# DRV8701-sch-pcb.net
KiCad netlist of a schematic drawn in EasyEDA Pro
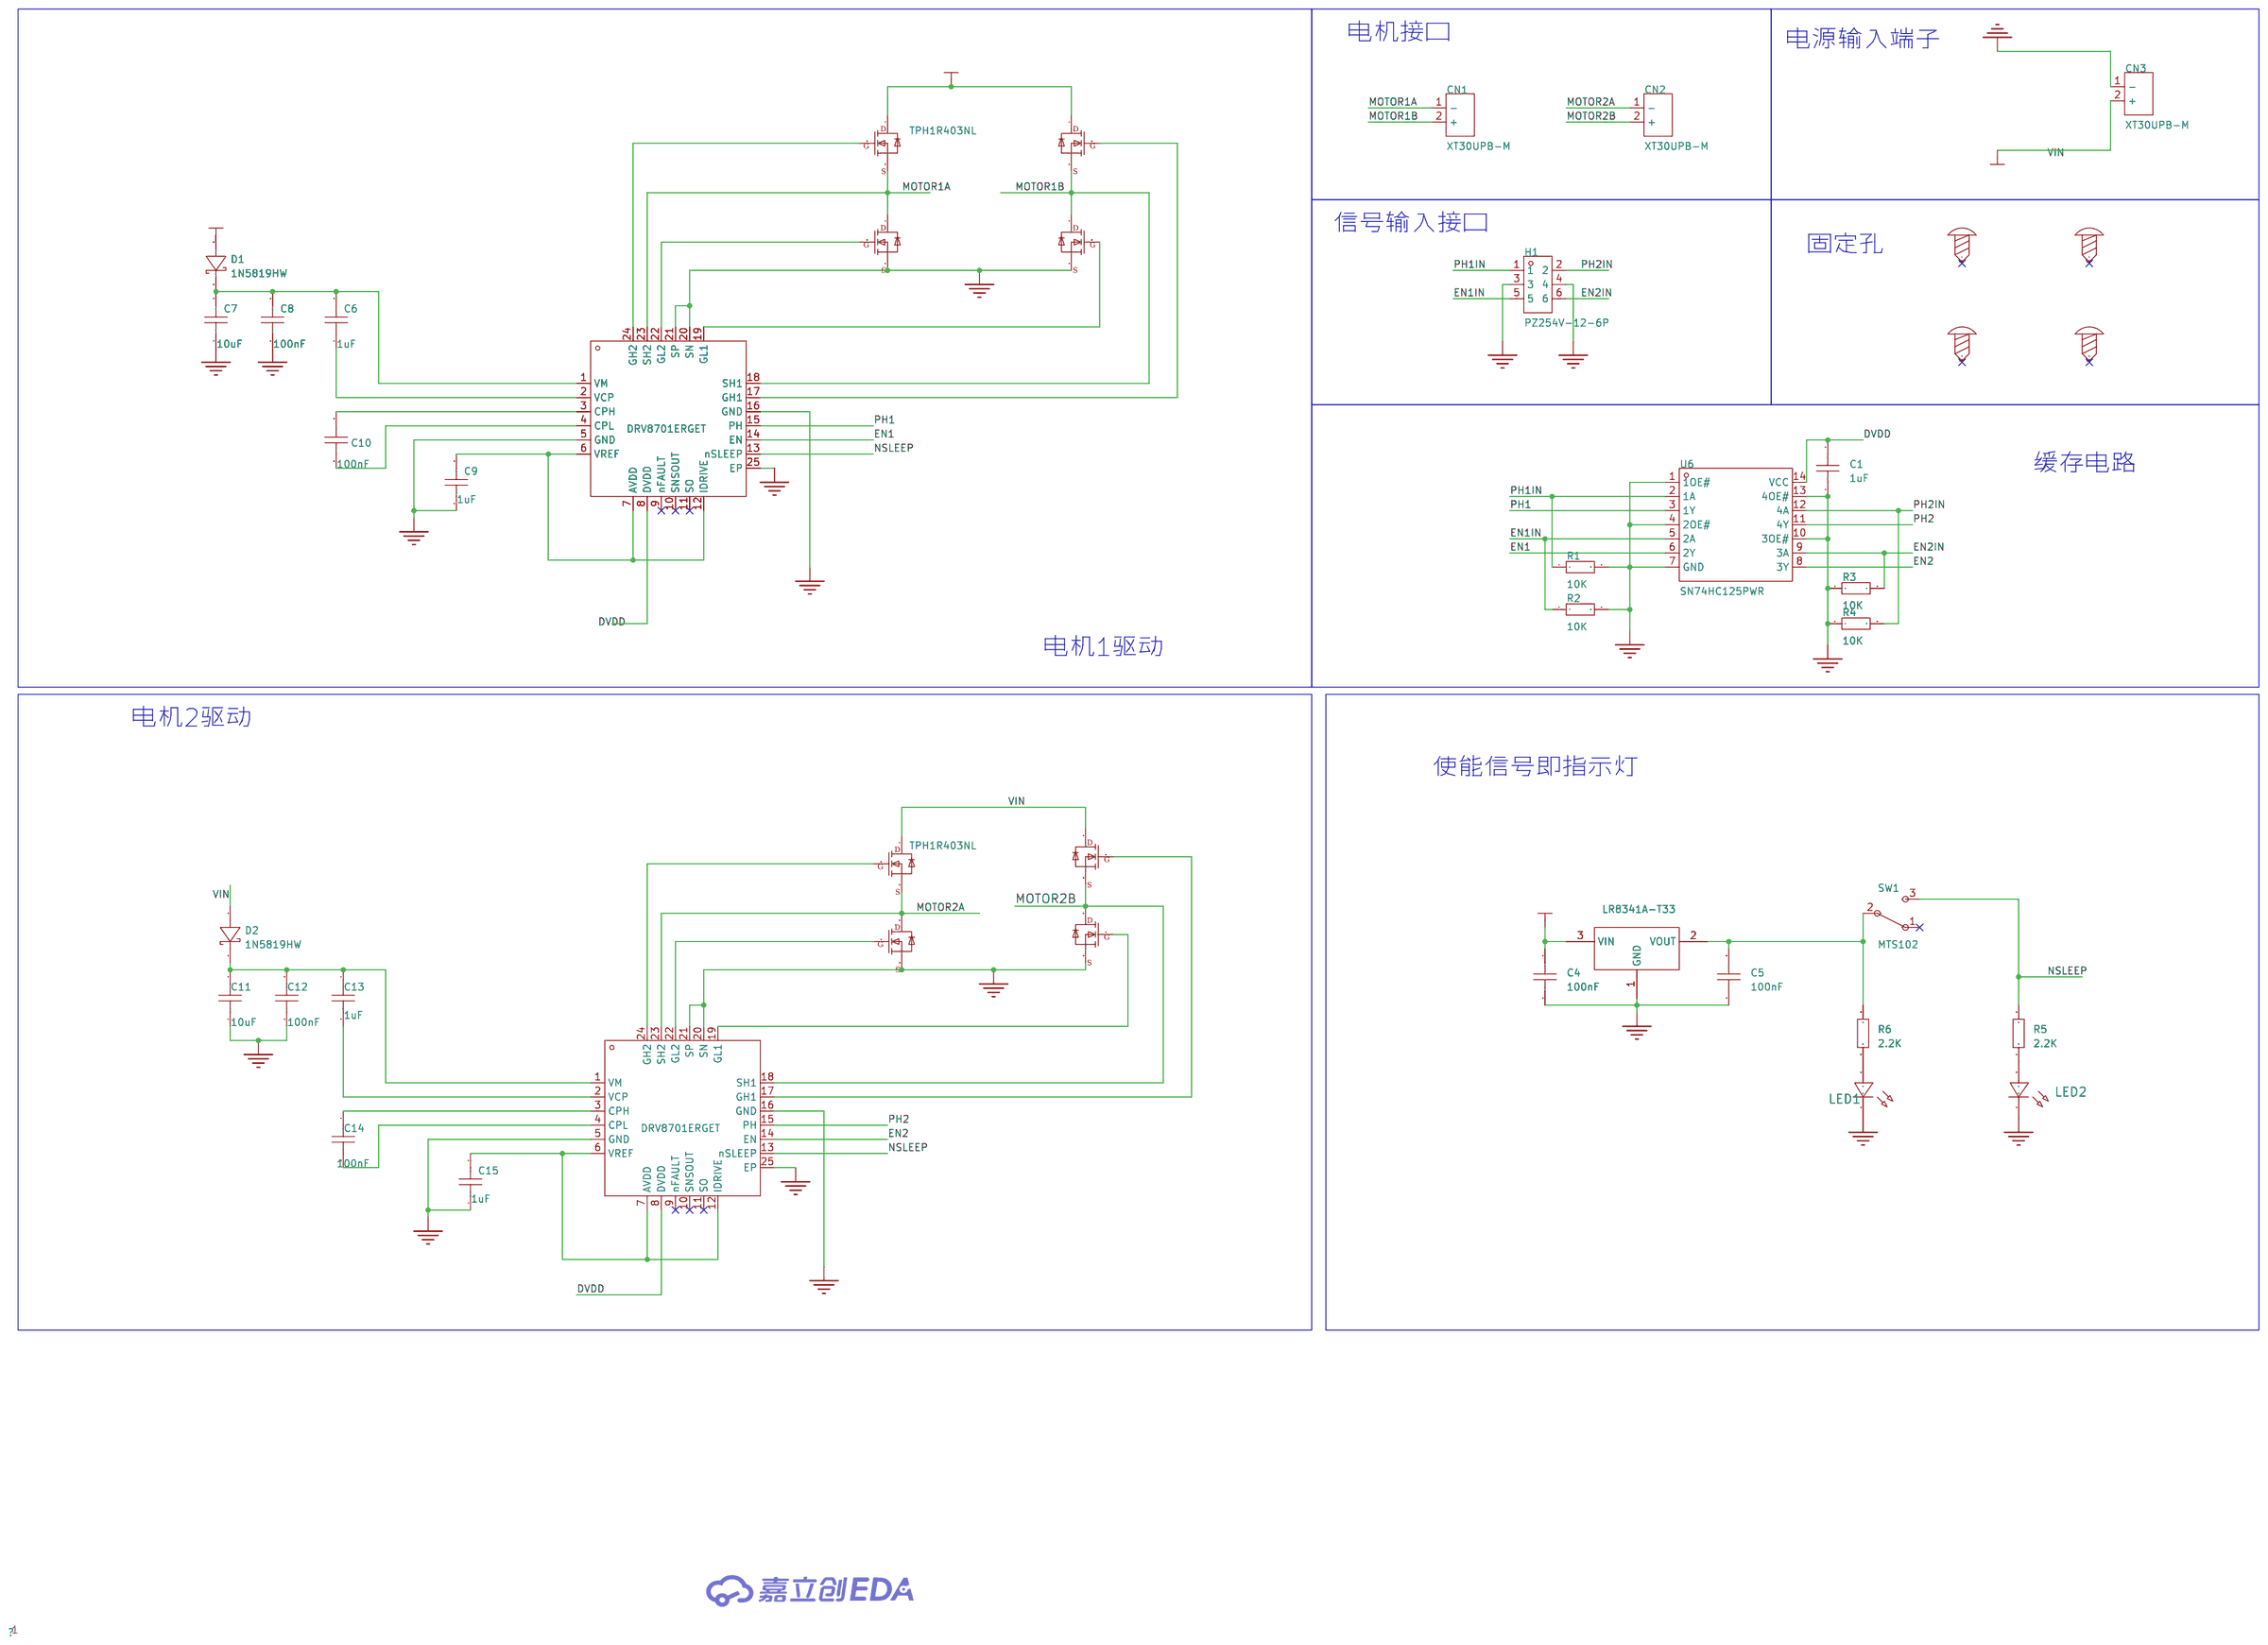
[diagram p0: schematic sheet]

(export (version "E")
  (design (tool "Eeschema 10.0.6"))
  (components
    (comp (ref "C1")
      (value "1uF")
      (footprint "easyedapro:C0603")
      (libsource (lib "easyedapro") (part "Capacitance"))
    )
    (comp (ref "C4")
      (value "100nF")
      (footprint "easyedapro:C0603")
      (libsource (lib "easyedapro") (part "Capacitance"))
    )
    (comp (ref "C5")
      (value "100nF")
      (footprint "easyedapro:C0603")
      (libsource (lib "easyedapro") (part "Capacitance"))
    )
    (comp (ref "C6")
      (value "1uF")
      (footprint "easyedapro:C0603")
      (libsource (lib "easyedapro") (part "Capacitance"))
    )
    (comp (ref "C7")
      (value "10uF")
      (footprint "easyedapro:C0603")
      (libsource (lib "easyedapro") (part "Capacitance"))
    )
    (comp (ref "C8")
      (value "100nF")
      (footprint "easyedapro:C0603")
      (libsource (lib "easyedapro") (part "Capacitance"))
    )
    (comp (ref "C9")
      (value "1uF")
      (footprint "easyedapro:C0603")
      (libsource (lib "easyedapro") (part "Capacitance"))
    )
    (comp (ref "C10")
      (value "100nF")
      (footprint "easyedapro:C0603")
      (libsource (lib "easyedapro") (part "Capacitance"))
    )
    (comp (ref "C11")
      (value "10uF")
      (footprint "easyedapro:C0603")
      (libsource (lib "easyedapro") (part "Capacitance"))
    )
    (comp (ref "C12")
      (value "100nF")
      (footprint "easyedapro:C0603")
      (libsource (lib "easyedapro") (part "Capacitance"))
    )
    (comp (ref "C13")
      (value "1uF")
      (footprint "easyedapro:C0603")
      (libsource (lib "easyedapro") (part "Capacitance"))
    )
    (comp (ref "C14")
      (value "100nF")
      (footprint "easyedapro:C0603")
      (libsource (lib "easyedapro") (part "Capacitance"))
    )
    (comp (ref "C15")
      (value "1uF")
      (footprint "easyedapro:C0603")
      (libsource (lib "easyedapro") (part "Capacitance"))
    )
    (comp (ref "CN1")
      (value "XT30UPB-M")
      (footprint "easyedapro:CONN-TH_XT30UPB-M")
      (fields (field (name "Manufacturer") "Changzhou Amass Elec"))
      (libsource (lib "easyedapro") (part "XT30UPB-M"))
    )
    (comp (ref "CN2")
      (value "XT30UPB-M")
      (footprint "easyedapro:CONN-TH_XT30UPB-M")
      (fields (field (name "Manufacturer") "Changzhou Amass Elec"))
      (libsource (lib "easyedapro") (part "XT30UPB-M"))
    )
    (comp (ref "CN3")
      (value "XT30UPB-M")
      (footprint "easyedapro:CONN-TH_XT30UPB-M")
      (fields (field (name "Manufacturer") "Changzhou Amass Elec"))
      (libsource (lib "easyedapro") (part "XT30UPB-M"))
    )
    (comp (ref "D1")
      (value "1N5819HW")
      (footprint "easyedapro:SOD-123_L2.7-W1.6-LS3.7-RD-1")
      (description "二极管配置:-;正向压降(Vf):900mV@3A;直流反向耐压(Vr):40V;整流电流:1A;")
      (fields (field (name "Manufacturer") "TECH PUBLIC(台舟)"))
      (libsource (lib "easyedapro") (part "1N5819HW"))
    )
    (comp (ref "D2")
      (value "1N5819HW")
      (footprint "easyedapro:SOD-123_L2.7-W1.6-LS3.7-RD-1")
      (description "二极管配置:-;正向压降(Vf):900mV@3A;直流反向耐压(Vr):40V;整流电流:1A;")
      (fields (field (name "Manufacturer") "TECH PUBLIC(台舟)"))
      (libsource (lib "easyedapro") (part "1N5819HW"))
    )
    (comp (ref "H1")
      (value "PZ254V-12-6P")
      (footprint "easyedapro:HDR-TH_6P-P2.54-V-M-R2-C3-S2.54")
      (fields (field (name "Manufacturer") "XFCN(兴飞)"))
      (libsource (lib "easyedapro") (part "PZ254V-12-6P"))
    )
    (comp (ref "LED1")
      (value "~")
      (footprint "easyedapro:LED_0603")
      (libsource (lib "easyedapro") (part "LED_R"))
    )
    (comp (ref "LED2")
      (value "~")
      (footprint "easyedapro:LED_0603")
      (libsource (lib "easyedapro") (part "LED_R"))
    )
    (comp (ref "Q1")
      (value "TPH1R403NL")
      (footprint "easyedapro:DFN5x6")
      (libsource (lib "easyedapro") (part "TPH1R403NL"))
    )
    (comp (ref "Q3")
      (value "TPH1R403NL")
      (footprint "easyedapro:DFN5x6")
      (libsource (lib "easyedapro") (part "TPH1R403NL"))
    )
    (comp (ref "Q6")
      (value "TPH1R403NL")
      (footprint "easyedapro:DFN5x6")
      (libsource (lib "easyedapro") (part "TPH1R403NL"))
    )
    (comp (ref "Q7")
      (value "TPH1R403NL")
      (footprint "easyedapro:DFN5x6")
      (libsource (lib "easyedapro") (part "TPH1R403NL"))
    )
    (comp (ref "Q12")
      (value "TPH1R403NL")
      (footprint "easyedapro:DFN5x6")
      (libsource (lib "easyedapro") (part "TPH1R403NL"))
    )
    (comp (ref "Q13")
      (value "TPH1R403NL")
      (footprint "easyedapro:DFN5x6")
      (libsource (lib "easyedapro") (part "TPH1R403NL"))
    )
    (comp (ref "Q15")
      (value "TPH1R403NL")
      (footprint "easyedapro:DFN5x6")
      (libsource (lib "easyedapro") (part "TPH1R403NL"))
    )
    (comp (ref "Q16")
      (value "TPH1R403NL")
      (footprint "easyedapro:DFN5x6")
      (libsource (lib "easyedapro") (part "TPH1R403NL"))
    )
    (comp (ref "R1") (value "10K") (footprint "easyedapro:R0603") (libsource (lib "easyedapro") (part "电阻")))
    (comp (ref "R2") (value "10K") (footprint "easyedapro:R0603") (libsource (lib "easyedapro") (part "电阻")))
    (comp (ref "R3") (value "10K") (footprint "easyedapro:R0603") (libsource (lib "easyedapro") (part "电阻")))
    (comp (ref "R4") (value "10K") (footprint "easyedapro:R0603") (libsource (lib "easyedapro") (part "电阻")))
    (comp (ref "R5") (value "2.2K") (footprint "easyedapro:R0603") (libsource (lib "easyedapro") (part "电阻")))
    (comp (ref "R6") (value "2.2K") (footprint "easyedapro:R0603") (libsource (lib "easyedapro") (part "电阻")))
    (comp (ref "SCREW1")
      (value "~")
      (footprint "easyedapro:M3螺丝")
      (libsource (lib "easyedapro") (part "螺丝孔"))
    )
    (comp (ref "SCREW2")
      (value "~")
      (footprint "easyedapro:M3螺丝")
      (libsource (lib "easyedapro") (part "螺丝孔"))
    )
    (comp (ref "SCREW3")
      (value "~")
      (footprint "easyedapro:M3螺丝")
      (libsource (lib "easyedapro") (part "螺丝孔"))
    )
    (comp (ref "SCREW4")
      (value "~")
      (footprint "easyedapro:M3螺丝")
      (libsource (lib "easyedapro") (part "螺丝孔"))
    )
    (comp (ref "SW1")
      (value "MTS102")
      (footprint "easyedapro:MTS102")
      (libsource (lib "easyedapro") (part "MTS102"))
    )
    (comp (ref "U2")
      (value "DRV8701ERGET")
      (footprint "easyedapro:VQFN-24_L4.0-W4.0-P0.50-BL-EP2.5")
      (description "DRV8701 47V H 桥智能栅极驱动器")
      (fields (field (name "Manufacturer") "TI(德州仪器)"))
      (libsource (lib "easyedapro") (part "DRV8701ERGET"))
    )
    (comp (ref "U3")
      (value "DRV8701ERGET")
      (footprint "easyedapro:VQFN-24_L4.0-W4.0-P0.50-BL-EP2.5")
      (description "DRV8701 47V H 桥智能栅极驱动器")
      (fields (field (name "Manufacturer") "TI(德州仪器)"))
      (libsource (lib "easyedapro") (part "DRV8701ERGET"))
    )
    (comp (ref "U6")
      (value "SN74HC125PWR")
      (footprint "easyedapro:TSSOP-14_L5.0-W4.4-P0.65-LS6.5-BL")
      (description "输入类型:-;工作电压:2V~6V;元件数:4;每个元件位数:1;灌电流(IOL):7.8mA;拉电流(IOH):7.8mA;")
      (fields (field (name "Manufacturer") "TI(德州仪器)"))
      (libsource (lib "easyedapro") (part "SN74HC125PWR"))
    )
    (comp (ref "U8")
      (value "LR8341A-T33")
      (footprint "easyedapro:SOT-23")
      (libsource (lib "easyedapro") (part "LR8341A-T33"))
    )
  )
  (nets
    (net (code "1") (name "/DVDD") (class "Default")
      (node (ref "C1") (pin "2") (pinfunction "2_2") (pintype "input"))
      (node (ref "U2") (pin "8") (pinfunction "DVDD_8") (pintype "unspecified"))
      (node (ref "U3") (pin "8") (pinfunction "DVDD_8") (pintype "unspecified"))
      (node (ref "U6") (pin "14") (pinfunction "VCC_14") (pintype "unspecified"))
    )
    (net (code "2") (name "/EN1") (class "Default")
      (node (ref "U2") (pin "14") (pinfunction "EN_14") (pintype "unspecified"))
      (node (ref "U6") (pin "6") (pinfunction "2Y_6") (pintype "unspecified"))
    )
    (net (code "3") (name "/EN1IN") (class "Default")
      (node (ref "H1") (pin "5") (pinfunction "5_5") (pintype "unspecified"))
      (node (ref "R2") (pin "1") (pinfunction "1_1") (pintype "input"))
      (node (ref "U6") (pin "5") (pinfunction "2A_5") (pintype "unspecified"))
    )
    (net (code "4") (name "/EN2") (class "Default")
      (node (ref "U3") (pin "14") (pinfunction "EN_14") (pintype "unspecified"))
      (node (ref "U6") (pin "8") (pinfunction "3Y_8") (pintype "unspecified"))
    )
    (net (code "5") (name "/EN2IN") (class "Default")
      (node (ref "H1") (pin "6") (pinfunction "6_6") (pintype "unspecified"))
      (node (ref "R3") (pin "2") (pinfunction "2_2") (pintype "input"))
      (node (ref "U6") (pin "9") (pinfunction "3A_9") (pintype "unspecified"))
    )
    (net (code "6") (name "/MOTOR1A") (class "Default")
      (node (ref "CN1") (pin "1") (pinfunction "-_1") (pintype "unspecified"))
      (node (ref "Q1") (pin "3") (pinfunction "S_3") (pintype "input"))
      (node (ref "Q3") (pin "1") (pinfunction "D_1") (pintype "input"))
      (node (ref "U2") (pin "23") (pinfunction "SH2_23") (pintype "unspecified"))
    )
    (net (code "7") (name "/MOTOR1B") (class "Default")
      (node (ref "CN1") (pin "2") (pinfunction "+_2") (pintype "unspecified"))
      (node (ref "Q12") (pin "1") (pinfunction "D_1") (pintype "input"))
      (node (ref "Q13") (pin "3") (pinfunction "S_3") (pintype "input"))
      (node (ref "U2") (pin "18") (pinfunction "SH1_18") (pintype "unspecified"))
    )
    (net (code "8") (name "/MOTOR2A") (class "Default")
      (node (ref "CN2") (pin "1") (pinfunction "-_1") (pintype "unspecified"))
      (node (ref "Q6") (pin "3") (pinfunction "S_3") (pintype "input"))
      (node (ref "Q7") (pin "1") (pinfunction "D_1") (pintype "input"))
      (node (ref "U3") (pin "23") (pinfunction "SH2_23") (pintype "unspecified"))
    )
    (net (code "9") (name "/MOTOR2B") (class "Default")
      (node (ref "CN2") (pin "2") (pinfunction "+_2") (pintype "unspecified"))
      (node (ref "Q15") (pin "3") (pinfunction "S_3") (pintype "input"))
      (node (ref "Q16") (pin "1") (pinfunction "D_1") (pintype "input"))
      (node (ref "U3") (pin "18") (pinfunction "SH1_18") (pintype "unspecified"))
    )
    (net (code "10") (name "/NSLEEP") (class "Default")
      (node (ref "R5") (pin "2") (pinfunction "2_2") (pintype "input"))
      (node (ref "SW1") (pin "3") (pinfunction "ON_3") (pintype "input"))
      (node (ref "U2") (pin "13") (pinfunction "nSLEEP_13") (pintype "unspecified"))
      (node (ref "U3") (pin "13") (pinfunction "nSLEEP_13") (pintype "unspecified"))
    )
    (net (code "11") (name "/PH1") (class "Default")
      (node (ref "U2") (pin "15") (pinfunction "PH_15") (pintype "unspecified"))
      (node (ref "U6") (pin "3") (pinfunction "1Y_3") (pintype "unspecified"))
    )
    (net (code "12") (name "/PH1IN") (class "Default")
      (node (ref "H1") (pin "1") (pinfunction "1_1") (pintype "unspecified"))
      (node (ref "R1") (pin "1") (pinfunction "1_1") (pintype "input"))
      (node (ref "U6") (pin "2") (pinfunction "1A_2") (pintype "unspecified"))
    )
    (net (code "13") (name "/PH2") (class "Default")
      (node (ref "U3") (pin "15") (pinfunction "PH_15") (pintype "unspecified"))
      (node (ref "U6") (pin "11") (pinfunction "4Y_11") (pintype "unspecified"))
    )
    (net (code "14") (name "/PH2IN") (class "Default")
      (node (ref "H1") (pin "2") (pinfunction "2_2") (pintype "unspecified"))
      (node (ref "R4") (pin "2") (pinfunction "2_2") (pintype "input"))
      (node (ref "U6") (pin "12") (pinfunction "4A_12") (pintype "unspecified"))
    )
    (net (code "15") (name "GND") (class "Default")
      (node (ref "C1") (pin "1") (pinfunction "1_1") (pintype "input"))
      (node (ref "C11") (pin "1") (pinfunction "1_1") (pintype "input"))
      (node (ref "C12") (pin "1") (pinfunction "1_1") (pintype "input"))
      (node (ref "C15") (pin "1") (pinfunction "1_1") (pintype "input"))
      (node (ref "C4") (pin "1") (pinfunction "1_1") (pintype "input"))
      (node (ref "C5") (pin "1") (pinfunction "1_1") (pintype "input"))
      (node (ref "C7") (pin "1") (pinfunction "1_1") (pintype "input"))
      (node (ref "C8") (pin "1") (pinfunction "1_1") (pintype "input"))
      (node (ref "C9") (pin "1") (pinfunction "1_1") (pintype "input"))
      (node (ref "CN3") (pin "1") (pinfunction "-_1") (pintype "unspecified"))
      (node (ref "H1") (pin "3") (pinfunction "3_3") (pintype "unspecified"))
      (node (ref "H1") (pin "4") (pinfunction "4_4") (pintype "unspecified"))
      (node (ref "LED1") (pin "1") (pinfunction "C_1") (pintype "input"))
      (node (ref "LED2") (pin "1") (pinfunction "C_1") (pintype "input"))
      (node (ref "Q12") (pin "3") (pinfunction "S_3") (pintype "input"))
      (node (ref "Q16") (pin "3") (pinfunction "S_3") (pintype "input"))
      (node (ref "Q3") (pin "3") (pinfunction "S_3") (pintype "input"))
      (node (ref "Q7") (pin "3") (pinfunction "S_3") (pintype "input"))
      (node (ref "R1") (pin "2") (pinfunction "2_2") (pintype "input"))
      (node (ref "R2") (pin "2") (pinfunction "2_2") (pintype "input"))
      (node (ref "R3") (pin "1") (pinfunction "1_1") (pintype "input"))
      (node (ref "R4") (pin "1") (pinfunction "1_1") (pintype "input"))
      (node (ref "U2") (pin "16") (pinfunction "GND_16") (pintype "unspecified"))
      (node (ref "U2") (pin "20") (pinfunction "SN_20") (pintype "unspecified"))
      (node (ref "U2") (pin "21") (pinfunction "SP_21") (pintype "unspecified"))
      (node (ref "U2") (pin "25") (pinfunction "EP_25") (pintype "unspecified"))
      (node (ref "U2") (pin "5") (pinfunction "GND_5") (pintype "unspecified"))
      (node (ref "U3") (pin "16") (pinfunction "GND_16") (pintype "unspecified"))
      (node (ref "U3") (pin "20") (pinfunction "SN_20") (pintype "unspecified"))
      (node (ref "U3") (pin "21") (pinfunction "SP_21") (pintype "unspecified"))
      (node (ref "U3") (pin "25") (pinfunction "EP_25") (pintype "unspecified"))
      (node (ref "U3") (pin "5") (pinfunction "GND_5") (pintype "unspecified"))
      (node (ref "U6") (pin "1") (pinfunction "1OE#_1") (pintype "unspecified"))
      (node (ref "U6") (pin "10") (pinfunction "3OE#_10") (pintype "unspecified"))
      (node (ref "U6") (pin "13") (pinfunction "4OE#_13") (pintype "unspecified"))
      (node (ref "U6") (pin "4") (pinfunction "2OE#_4") (pintype "unspecified"))
      (node (ref "U6") (pin "7") (pinfunction "GND_7") (pintype "unspecified"))
      (node (ref "U8") (pin "1") (pinfunction "GND_1") (pintype "unspecified"))
    )
    (net (code "16") (name "Net-(D1-K)") (class "Default")
      (node (ref "C6") (pin "2") (pinfunction "2_2") (pintype "input"))
      (node (ref "C7") (pin "2") (pinfunction "2_2") (pintype "input"))
      (node (ref "C8") (pin "2") (pinfunction "2_2") (pintype "input"))
      (node (ref "D1") (pin "1") (pinfunction "K_1") (pintype "unspecified"))
      (node (ref "U2") (pin "1") (pinfunction "VM_1") (pintype "unspecified"))
    )
    (net (code "17") (name "Net-(D2-K)") (class "Default")
      (node (ref "C11") (pin "2") (pinfunction "2_2") (pintype "input"))
      (node (ref "C12") (pin "2") (pinfunction "2_2") (pintype "input"))
      (node (ref "C13") (pin "1") (pinfunction "1_1") (pintype "input"))
      (node (ref "D2") (pin "1") (pinfunction "K_1") (pintype "unspecified"))
      (node (ref "U3") (pin "1") (pinfunction "VM_1") (pintype "unspecified"))
    )
    (net (code "18") (name "Net-(LED1-A)") (class "Default")
      (node (ref "LED1") (pin "2") (pinfunction "A_2") (pintype "input"))
      (node (ref "R6") (pin "1") (pinfunction "1_1") (pintype "input"))
    )
    (net (code "19") (name "Net-(LED2-A)") (class "Default")
      (node (ref "LED2") (pin "2") (pinfunction "A_2") (pintype "input"))
      (node (ref "R5") (pin "1") (pinfunction "1_1") (pintype "input"))
    )
    (net (code "20") (name "Net-(Q1-G)") (class "Default")
      (node (ref "Q1") (pin "2") (pinfunction "G_2") (pintype "input"))
      (node (ref "U2") (pin "24") (pinfunction "GH2_24") (pintype "unspecified"))
    )
    (net (code "21") (name "Net-(Q3-G)") (class "Default")
      (node (ref "Q3") (pin "2") (pinfunction "G_2") (pintype "input"))
      (node (ref "U2") (pin "22") (pinfunction "GL2_22") (pintype "unspecified"))
    )
    (net (code "22") (name "Net-(Q6-G)") (class "Default")
      (node (ref "Q6") (pin "2") (pinfunction "G_2") (pintype "input"))
      (node (ref "U3") (pin "24") (pinfunction "GH2_24") (pintype "unspecified"))
    )
    (net (code "23") (name "Net-(Q7-G)") (class "Default")
      (node (ref "Q7") (pin "2") (pinfunction "G_2") (pintype "input"))
      (node (ref "U3") (pin "22") (pinfunction "GL2_22") (pintype "unspecified"))
    )
    (net (code "24") (name "Net-(Q12-G)") (class "Default")
      (node (ref "Q12") (pin "2") (pinfunction "G_2") (pintype "input"))
      (node (ref "U2") (pin "19") (pinfunction "GL1_19") (pintype "unspecified"))
    )
    (net (code "25") (name "Net-(Q13-G)") (class "Default")
      (node (ref "Q13") (pin "2") (pinfunction "G_2") (pintype "input"))
      (node (ref "U2") (pin "17") (pinfunction "GH1_17") (pintype "unspecified"))
    )
    (net (code "26") (name "Net-(Q15-G)") (class "Default")
      (node (ref "Q15") (pin "2") (pinfunction "G_2") (pintype "input"))
      (node (ref "U3") (pin "17") (pinfunction "GH1_17") (pintype "unspecified"))
    )
    (net (code "27") (name "Net-(Q16-G)") (class "Default")
      (node (ref "Q16") (pin "2") (pinfunction "G_2") (pintype "input"))
      (node (ref "U3") (pin "19") (pinfunction "GL1_19") (pintype "unspecified"))
    )
    (net (code "28") (name "Net-(SW1-OFF)") (class "Default")
      (node (ref "C5") (pin "2") (pinfunction "2_2") (pintype "input"))
      (node (ref "R6") (pin "2") (pinfunction "2_2") (pintype "input"))
      (node (ref "SW1") (pin "2") (pinfunction "OFF_2") (pintype "input"))
      (node (ref "U8") (pin "2") (pinfunction "VOUT_2") (pintype "unspecified"))
    )
    (net (code "29") (name "Net-(U2-AVDD)") (class "Default")
      (node (ref "C9") (pin "2") (pinfunction "2_2") (pintype "input"))
      (node (ref "U2") (pin "12") (pinfunction "IDRIVE_12") (pintype "unspecified"))
      (node (ref "U2") (pin "6") (pinfunction "VREF_6") (pintype "unspecified"))
      (node (ref "U2") (pin "7") (pinfunction "AVDD_7") (pintype "unspecified"))
    )
    (net (code "30") (name "Net-(U2-CPH)") (class "Default")
      (node (ref "C10") (pin "2") (pinfunction "2_2") (pintype "input"))
      (node (ref "U2") (pin "3") (pinfunction "CPH_3") (pintype "unspecified"))
    )
    (net (code "31") (name "Net-(U2-CPL)") (class "Default")
      (node (ref "C10") (pin "1") (pinfunction "1_1") (pintype "input"))
      (node (ref "U2") (pin "4") (pinfunction "CPL_4") (pintype "unspecified"))
    )
    (net (code "32") (name "Net-(U2-VCP)") (class "Default")
      (node (ref "C6") (pin "1") (pinfunction "1_1") (pintype "input"))
      (node (ref "U2") (pin "2") (pinfunction "VCP_2") (pintype "unspecified"))
    )
    (net (code "33") (name "Net-(U3-AVDD)") (class "Default")
      (node (ref "C15") (pin "2") (pinfunction "2_2") (pintype "input"))
      (node (ref "U3") (pin "12") (pinfunction "IDRIVE_12") (pintype "unspecified"))
      (node (ref "U3") (pin "6") (pinfunction "VREF_6") (pintype "unspecified"))
      (node (ref "U3") (pin "7") (pinfunction "AVDD_7") (pintype "unspecified"))
    )
    (net (code "34") (name "Net-(U3-CPH)") (class "Default")
      (node (ref "C14") (pin "1") (pinfunction "1_1") (pintype "input"))
      (node (ref "U3") (pin "3") (pinfunction "CPH_3") (pintype "unspecified"))
    )
    (net (code "35") (name "Net-(U3-CPL)") (class "Default")
      (node (ref "C14") (pin "2") (pinfunction "2_2") (pintype "input"))
      (node (ref "U3") (pin "4") (pinfunction "CPL_4") (pintype "unspecified"))
    )
    (net (code "36") (name "Net-(U3-VCP)") (class "Default")
      (node (ref "C13") (pin "2") (pinfunction "2_2") (pintype "input"))
      (node (ref "U3") (pin "2") (pinfunction "VCP_2") (pintype "unspecified"))
    )
    (net (code "37") (name "VIN") (class "Default")
      (node (ref "C4") (pin "2") (pinfunction "2_2") (pintype "input"))
      (node (ref "CN3") (pin "2") (pinfunction "+_2") (pintype "unspecified"))
      (node (ref "D1") (pin "2") (pinfunction "A_2") (pintype "unspecified"))
      (node (ref "D2") (pin "2") (pinfunction "A_2") (pintype "unspecified"))
      (node (ref "Q1") (pin "1") (pinfunction "D_1") (pintype "input"))
      (node (ref "Q13") (pin "1") (pinfunction "D_1") (pintype "input"))
      (node (ref "Q15") (pin "1") (pinfunction "D_1") (pintype "input"))
      (node (ref "Q6") (pin "1") (pinfunction "D_1") (pintype "input"))
      (node (ref "U8") (pin "3") (pinfunction "VIN_3") (pintype "unspecified"))
    )
    (net (code "38") (name "unconnected-(SCREW1-Pad1)") (class "Default")
      (node (ref "SCREW1") (pin "1") (pinfunction "1_1") (pintype "input+no_connect"))
    )
    (net (code "39") (name "unconnected-(SCREW2-Pad1)") (class "Default")
      (node (ref "SCREW2") (pin "1") (pinfunction "1_1") (pintype "input+no_connect"))
    )
    (net (code "40") (name "unconnected-(SCREW3-Pad1)") (class "Default")
      (node (ref "SCREW3") (pin "1") (pinfunction "1_1") (pintype "input+no_connect"))
    )
    (net (code "41") (name "unconnected-(SCREW4-Pad1)") (class "Default")
      (node (ref "SCREW4") (pin "1") (pinfunction "1_1") (pintype "input+no_connect"))
    )
    (net (code "42") (name "unconnected-(SW1-ON-Pad1)") (class "Default")
      (node (ref "SW1") (pin "1") (pinfunction "ON_1") (pintype "input+no_connect"))
    )
    (net (code "43") (name "unconnected-(U2-SNSOUT-Pad10)") (class "Default")
      (node (ref "U2") (pin "10") (pinfunction "SNSOUT_10") (pintype "unspecified+no_connect"))
    )
    (net (code "44") (name "unconnected-(U2-SO-Pad11)") (class "Default")
      (node (ref "U2") (pin "11") (pinfunction "SO_11") (pintype "unspecified+no_connect"))
    )
    (net (code "45") (name "unconnected-(U2-nFAULT-Pad9)") (class "Default")
      (node (ref "U2") (pin "9") (pinfunction "nFAULT_9") (pintype "unspecified+no_connect"))
    )
    (net (code "46") (name "unconnected-(U3-SNSOUT-Pad10)") (class "Default")
      (node (ref "U3") (pin "10") (pinfunction "SNSOUT_10") (pintype "unspecified+no_connect"))
    )
    (net (code "47") (name "unconnected-(U3-SO-Pad11)") (class "Default")
      (node (ref "U3") (pin "11") (pinfunction "SO_11") (pintype "unspecified+no_connect"))
    )
    (net (code "48") (name "unconnected-(U3-nFAULT-Pad9)") (class "Default")
      (node (ref "U3") (pin "9") (pinfunction "nFAULT_9") (pintype "unspecified+no_connect"))
    )
  )
)
